# 05-SD_CARD.net
KiCad netlist of a schematic drawn in Altium Designer
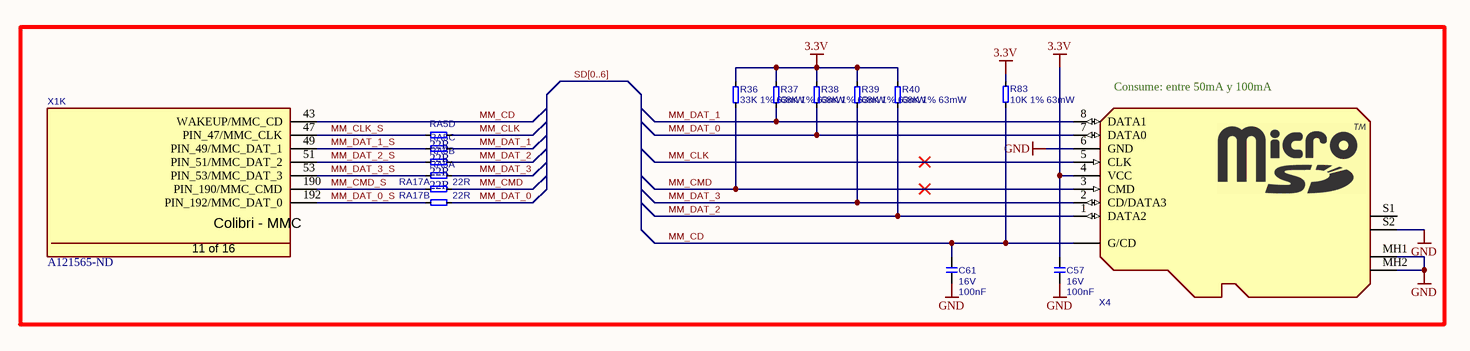
[diagram p0: 05-SD CARD.SchDoc]

(export (version "E")
  (design (tool "Eeschema 10.0.6"))
  (components
    (comp (ref "C57")
      (value "100nF")
      (footprint "CAPC1005X60N")
      (description "Capacitor Ceramic X7R 100nF 16V 10% 0603")
      (fields
        (field (name "TOLERANCE") "10%")
        (field (name "RATING") "16V")
        (field (name "Comment") "100nF 16V 10% X7R")
      )
      (libsource (lib "AI Gateway - Carrier") (part "C-100nF-16V-10%-0603"))
    )
    (comp (ref "C61")
      (value "100nF")
      (footprint "CAPC1005X60N")
      (description "Capacitor Ceramic X7R 100nF 16V 10% 0603")
      (fields
        (field (name "TOLERANCE") "10%")
        (field (name "RATING") "16V")
        (field (name "Comment") "100nF 16V 10% X7R")
      )
      (libsource (lib "AI Gateway - Carrier") (part "C-100nF-16V-10%-0603"))
    )
    (comp (ref "R36")
      (value "33K 1% 63mW")
      (footprint "RESC1005X40N")
      (description "Resistor 33Kohm 63mW 1% 0402")
      (fields (field (name "POWER") "63mW") (field (name "TOLERANCE") "1%"))
      (libsource (lib "AI Gateway - Carrier") (part "R-33K-1%-0402"))
    )
    (comp (ref "R37")
      (value "68K 1% 63mW")
      (footprint "RESC1005X40N")
      (description "Resistor 68Kohm 63mW 1% 0402")
      (fields
        (field (name "POWER") "63mW")
        (field (name "TOLERANCE") "1%")
        (field (name "SYMBOL CHECKED") "T")
      )
      (libsource (lib "AI Gateway - Carrier") (part "R-68K-1%-0402_1"))
    )
    (comp (ref "R38")
      (value "68K 1% 63mW")
      (footprint "RESC1005X40N")
      (description "Resistor 68Kohm 63mW 1% 0402")
      (fields
        (field (name "POWER") "63mW")
        (field (name "TOLERANCE") "1%")
        (field (name "SYMBOL CHECKED") "T")
      )
      (libsource (lib "AI Gateway - Carrier") (part "R-68K-1%-0402_1"))
    )
    (comp (ref "R39")
      (value "68K 1% 63mW")
      (footprint "RESC1005X40N")
      (description "Resistor 68Kohm 63mW 1% 0402")
      (fields
        (field (name "POWER") "63mW")
        (field (name "TOLERANCE") "1%")
        (field (name "SYMBOL CHECKED") "T")
      )
      (libsource (lib "AI Gateway - Carrier") (part "R-68K-1%-0402_1"))
    )
    (comp (ref "R40")
      (value "68K 1% 63mW")
      (footprint "RESC1005X40N")
      (description "Resistor 68Kohm 63mW 1% 0402")
      (fields
        (field (name "POWER") "63mW")
        (field (name "TOLERANCE") "1%")
        (field (name "SYMBOL CHECKED") "T")
      )
      (libsource (lib "AI Gateway - Carrier") (part "R-68K-1%-0402_1"))
    )
    (comp (ref "R83")
      (value "10K 1% 63mW")
      (footprint "RESC1005X40N")
      (description "Resistor 10Kohm 63mW 1% 0402")
      (fields (field (name "POWER") "63mW") (field (name "TOLERANCE") "1%"))
      (libsource (lib "AI Gateway - Carrier") (part "R-10K-1%-0402"))
    )
    (comp (ref "RA5")
      (value "22R")
      (footprint "T_Resistor_Array_X4")
      (description "Resistor Array 22 R 63mW 5% 1206")
      (fields (field (name "TOLERANCE") "5%") (field (name "MFG") "Generic"))
      (libsource (lib "Passive") (part "RA-22R-5%-1206-div"))
    )
    (comp (ref "RA17")
      (value "22R")
      (footprint "T_Resistor_Array_X4")
      (description "Resistor Array 22 R 63mW 5% 1206")
      (fields (field (name "TOLERANCE") "5%") (field (name "MFG") "Generic"))
      (libsource (lib "Passive") (part "RA-22R-5%-1206-div"))
    )
    (comp (ref "X1")
      (value "1473005-1")
      (footprint "T_Tyco_1473005-1")
      (description "SODIMM Connector")
      (fields (field (name "SUPPLIER PART NUMBER 1") "A121565-ND"))
      (libsource (lib "Connectors") (part "CON-Tyco-1473005-1-200-0.6mm"))
    )
    (comp (ref "X4")
      (value "MEM2051-00-195-00-A")
      (footprint "101-00660-68-6+MEM2051-00-195-00-A_REVC")
      (description "9 (8 + 1) Position Card Connector microSD™ Surface Mount, Right Angle Gold")
      (fields (field (name "MFG") "GCT"))
      (libsource (lib "AI Gateway - Carrier") (part "CON-GCT-SD-MEM2051-00-195-00-A"))
    )
  )
  (nets
    (net (code "8") (name "/MM_CD") (class "Default")
      (node (ref "C61") (pin "2") (pinfunction "2_2") (pintype "passive"))
      (node (ref "R83") (pin "2") (pinfunction "2_2") (pintype "passive"))
      (node (ref "X1") (pin "43") (pinfunction "WAKEUP/MMC_CD_43") (pintype "passive"))
      (node (ref "X4") (pin "G1") (pinfunction "G/CD_G1") (pintype "passive"))
    )
    (net (code "9") (name "/MM_CLK") (class "Default")
      (node (ref "RA5") (pin "4") (pinfunction "4_4") (pintype "passive"))
      (node (ref "X4") (pin "5") (pinfunction "CLK_5") (pintype "input"))
    )
    (net (code "10") (name "/MM_CLK_S") (class "Default")
      (node (ref "RA5") (pin "8") (pinfunction "8_8") (pintype "passive"))
      (node (ref "X1") (pin "47") (pinfunction "PIN_47/MMC_CLK_47") (pintype "passive"))
    )
    (net (code "11") (name "/MM_CMD") (class "Default")
      (node (ref "R36") (pin "1") (pinfunction "1_1") (pintype "passive"))
      (node (ref "RA17") (pin "5") (pinfunction "5_5") (pintype "passive"))
      (node (ref "X4") (pin "3") (pinfunction "CMD_3") (pintype "input"))
    )
    (net (code "12") (name "/MM_CMD_S") (class "Default")
      (node (ref "RA17") (pin "1") (pinfunction "1_1") (pintype "passive"))
      (node (ref "X1") (pin "190") (pinfunction "PIN_190/MMC_CMD_190") (pintype "passive"))
    )
    (net (code "13") (name "/MM_DAT_0") (class "Default")
      (node (ref "R38") (pin "1") (pinfunction "1_1") (pintype "passive"))
      (node (ref "RA17") (pin "6") (pinfunction "6_6") (pintype "passive"))
      (node (ref "X4") (pin "7") (pinfunction "DATA0_7") (pintype "bidirectional"))
    )
    (net (code "14") (name "/MM_DAT_0_S") (class "Default")
      (node (ref "RA17") (pin "2") (pinfunction "2_2") (pintype "passive"))
      (node (ref "X1") (pin "192") (pinfunction "PIN_192/MMC_DAT_0_192") (pintype "passive"))
    )
    (net (code "15") (name "/MM_DAT_1") (class "Default")
      (node (ref "R37") (pin "1") (pinfunction "1_1") (pintype "passive"))
      (node (ref "RA5") (pin "3") (pinfunction "3_3") (pintype "passive"))
      (node (ref "X4") (pin "8") (pinfunction "DATA1_8") (pintype "bidirectional"))
    )
    (net (code "16") (name "/MM_DAT_1_S") (class "Default")
      (node (ref "RA5") (pin "7") (pinfunction "7_7") (pintype "passive"))
      (node (ref "X1") (pin "49") (pinfunction "PIN_49/MMC_DAT_1_49") (pintype "passive"))
    )
    (net (code "17") (name "/MM_DAT_2") (class "Default")
      (node (ref "R40") (pin "1") (pinfunction "1_1") (pintype "passive"))
      (node (ref "RA5") (pin "2") (pinfunction "2_2") (pintype "passive"))
      (node (ref "X4") (pin "1") (pinfunction "DATA2_1") (pintype "bidirectional"))
    )
    (net (code "18") (name "/MM_DAT_2_S") (class "Default")
      (node (ref "RA5") (pin "6") (pinfunction "6_6") (pintype "passive"))
      (node (ref "X1") (pin "51") (pinfunction "PIN_51/MMC_DAT_2_51") (pintype "passive"))
    )
    (net (code "19") (name "/MM_DAT_3") (class "Default")
      (node (ref "R39") (pin "1") (pinfunction "1_1") (pintype "passive"))
      (node (ref "RA5") (pin "1") (pinfunction "1_1") (pintype "passive"))
      (node (ref "X4") (pin "2") (pinfunction "CD/DATA3_2") (pintype "bidirectional"))
    )
    (net (code "20") (name "/MM_DAT_3_S") (class "Default")
      (node (ref "RA5") (pin "5") (pinfunction "5_5") (pintype "passive"))
      (node (ref "X1") (pin "53") (pinfunction "PIN_53/MMC_DAT_3_53") (pintype "passive"))
    )
    (net (code "22") (name "3.3V") (class "Default")
      (node (ref "C57") (pin "2") (pinfunction "2_2") (pintype "passive"))
      (node (ref "R36") (pin "2") (pinfunction "2_2") (pintype "passive"))
      (node (ref "R37") (pin "2") (pinfunction "2_2") (pintype "passive"))
      (node (ref "R38") (pin "2") (pinfunction "2_2") (pintype "passive"))
      (node (ref "R39") (pin "2") (pinfunction "2_2") (pintype "passive"))
      (node (ref "R40") (pin "2") (pinfunction "2_2") (pintype "passive"))
      (node (ref "R83") (pin "1") (pinfunction "1_1") (pintype "passive"))
      (node (ref "X4") (pin "4") (pinfunction "VCC_4") (pintype "passive"))
    )
    (net (code "23") (name "GND") (class "Default")
      (node (ref "C57") (pin "1") (pinfunction "1_1") (pintype "passive"))
      (node (ref "C61") (pin "1") (pinfunction "1_1") (pintype "passive"))
      (node (ref "X4") (pin "6") (pinfunction "GND_6") (pintype "power_in"))
      (node (ref "X4") (pin "MH1") (pinfunction "S_MH1") (pintype "passive"))
      (node (ref "X4") (pin "MH2") (pinfunction "S_MH2") (pintype "passive"))
      (node (ref "X4") (pin "S2") (pinfunction "S2_S2") (pintype "passive"))
    )
    (net (code "24") (name "unconnected-(X4-PadS1)") (class "Default")
      (node (ref "X4") (pin "S1") (pinfunction "S1_S1") (pintype "passive"))
    )
  )
)
